# LED_Board.net
KiCad netlist of a schematic drawn in Altium Designer
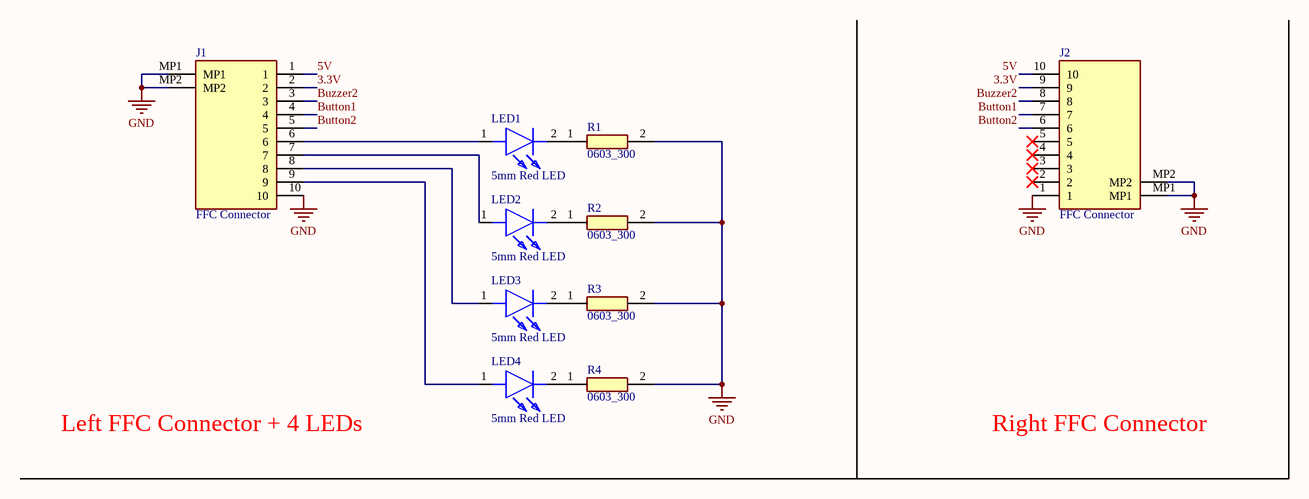
[diagram p0: LED Board.SchDoc]

(export (version "E")
  (design (tool "Eeschema 10.0.6"))
  (components
    (comp (ref "J1")
      (value "FFC Connector")
      (footprint "SamacSys:528921033")
      (description "Connector")
      (fields (field (name "MANUFACTURER_PART_NUMBER") "52892-1033"))
      (libsource (lib "") (part "FFC Connector_1"))
    )
    (comp (ref "J2")
      (value "FFC Connector")
      (footprint "SamacSys:528921033")
      (description "Connector")
      (fields (field (name "MANUFACTURER_PART_NUMBER") "52892-1033"))
      (libsource (lib "LED Board SCH Lib") (part "FFC Connector"))
    )
    (comp (ref "LED1")
      (value "5mm Red LED")
      (footprint "TLHR_6400")
      (description "LED")
      (fields (field (name "MANUFACTURER_PART_NUMBER") "TLHR6400"))
      (libsource (lib "LED Board SCH Lib") (part "TLHR6400"))
    )
    (comp (ref "LED2")
      (value "5mm Red LED")
      (footprint "TLHR_6400")
      (description "LED")
      (fields (field (name "MANUFACTURER_PART_NUMBER") "TLHR6400"))
      (libsource (lib "LED Board SCH Lib") (part "TLHR6400"))
    )
    (comp (ref "LED3")
      (value "5mm Red LED")
      (footprint "TLHR_6400")
      (description "LED")
      (fields (field (name "MANUFACTURER_PART_NUMBER") "TLHR6400"))
      (libsource (lib "LED Board SCH Lib") (part "TLHR6400"))
    )
    (comp (ref "LED4")
      (value "5mm Red LED")
      (footprint "TLHR_6400")
      (description "LED")
      (fields (field (name "MANUFACTURER_PART_NUMBER") "TLHR6400"))
      (libsource (lib "LED Board SCH Lib") (part "TLHR6400"))
    )
    (comp (ref "R1")
      (value "0603_300")
      (footprint "SamacSys:ERA3KV_(0603)")
      (description "Resistor")
      (fields (field (name "MANUFACTURER_PART_NUMBER") "ERA-3KEB2403V"))
      (libsource (lib "LED Board SCH Lib") (part "0603_R"))
    )
    (comp (ref "R2")
      (value "0603_300")
      (footprint "SamacSys:ERA3KV_(0603)")
      (description "Resistor")
      (fields (field (name "MANUFACTURER_PART_NUMBER") "ERA-3KEB2403V"))
      (libsource (lib "LED Board SCH Lib") (part "0603_R"))
    )
    (comp (ref "R3")
      (value "0603_300")
      (footprint "SamacSys:ERA3KV_(0603)")
      (description "Resistor")
      (fields (field (name "MANUFACTURER_PART_NUMBER") "ERA-3KEB2403V"))
      (libsource (lib "LED Board SCH Lib") (part "0603_R"))
    )
    (comp (ref "R4")
      (value "0603_300")
      (footprint "SamacSys:ERA3KV_(0603)")
      (description "Resistor")
      (fields (field (name "MANUFACTURER_PART_NUMBER") "ERA-3KEB2403V"))
      (libsource (lib "LED Board SCH Lib") (part "0603_R"))
    )
  )
  (nets
    (net (code "1") (name "/3.3V") (class "Default")
      (node (ref "J1") (pin "2") (pinfunction "2_2") (pintype "passive"))
      (node (ref "J2") (pin "9") (pinfunction "9_9") (pintype "passive"))
    )
    (net (code "2") (name "/5V") (class "Default")
      (node (ref "J1") (pin "1") (pinfunction "1_1") (pintype "passive"))
      (node (ref "J2") (pin "10") (pinfunction "10_10") (pintype "passive"))
    )
    (net (code "3") (name "/Button1") (class "Default")
      (node (ref "J1") (pin "4") (pinfunction "4_4") (pintype "passive"))
      (node (ref "J2") (pin "7") (pinfunction "7_7") (pintype "passive"))
    )
    (net (code "4") (name "/Button2") (class "Default")
      (node (ref "J1") (pin "5") (pinfunction "5_5") (pintype "passive"))
      (node (ref "J2") (pin "6") (pinfunction "6_6") (pintype "passive"))
    )
    (net (code "5") (name "/Buzzer2") (class "Default")
      (node (ref "J1") (pin "3") (pinfunction "3_3") (pintype "passive"))
      (node (ref "J2") (pin "8") (pinfunction "8_8") (pintype "passive"))
    )
    (net (code "6") (name "GND") (class "Default")
      (node (ref "J1") (pin "10") (pinfunction "10_10") (pintype "passive"))
      (node (ref "J1") (pin "MP1") (pinfunction "MP1_MP1") (pintype "passive"))
      (node (ref "J1") (pin "MP2") (pinfunction "MP2_MP2") (pintype "passive"))
      (node (ref "J2") (pin "1") (pinfunction "1_1") (pintype "passive"))
      (node (ref "J2") (pin "MP1") (pinfunction "MP1_MP1") (pintype "passive"))
      (node (ref "J2") (pin "MP2") (pinfunction "MP2_MP2") (pintype "passive"))
      (node (ref "R1") (pin "2") (pinfunction "2_2") (pintype "passive"))
      (node (ref "R2") (pin "2") (pinfunction "2_2") (pintype "passive"))
      (node (ref "R3") (pin "2") (pinfunction "2_2") (pintype "passive"))
      (node (ref "R4") (pin "2") (pinfunction "2_2") (pintype "passive"))
    )
    (net (code "7") (name "Net-(LED1-A)") (class "Default")
      (node (ref "J1") (pin "6") (pinfunction "6_6") (pintype "passive"))
      (node (ref "LED1") (pin "1") (pinfunction "A_1") (pintype "passive"))
    )
    (net (code "8") (name "Net-(LED1-K)") (class "Default")
      (node (ref "LED1") (pin "2") (pinfunction "K_2") (pintype "passive"))
      (node (ref "R1") (pin "1") (pinfunction "1_1") (pintype "passive"))
    )
    (net (code "9") (name "Net-(LED2-A)") (class "Default")
      (node (ref "J1") (pin "7") (pinfunction "7_7") (pintype "passive"))
      (node (ref "LED2") (pin "1") (pinfunction "A_1") (pintype "passive"))
    )
    (net (code "10") (name "Net-(LED2-K)") (class "Default")
      (node (ref "LED2") (pin "2") (pinfunction "K_2") (pintype "passive"))
      (node (ref "R2") (pin "1") (pinfunction "1_1") (pintype "passive"))
    )
    (net (code "11") (name "Net-(LED3-A)") (class "Default")
      (node (ref "J1") (pin "8") (pinfunction "8_8") (pintype "passive"))
      (node (ref "LED3") (pin "1") (pinfunction "A_1") (pintype "passive"))
    )
    (net (code "12") (name "Net-(LED3-K)") (class "Default")
      (node (ref "LED3") (pin "2") (pinfunction "K_2") (pintype "passive"))
      (node (ref "R3") (pin "1") (pinfunction "1_1") (pintype "passive"))
    )
    (net (code "13") (name "Net-(LED4-A)") (class "Default")
      (node (ref "J1") (pin "9") (pinfunction "9_9") (pintype "passive"))
      (node (ref "LED4") (pin "1") (pinfunction "A_1") (pintype "passive"))
    )
    (net (code "14") (name "Net-(LED4-K)") (class "Default")
      (node (ref "LED4") (pin "2") (pinfunction "K_2") (pintype "passive"))
      (node (ref "R4") (pin "1") (pinfunction "1_1") (pintype "passive"))
    )
    (net (code "15") (name "unconnected-(J2-Pad2)") (class "Default")
      (node (ref "J2") (pin "2") (pinfunction "2_2") (pintype "passive+no_connect"))
    )
    (net (code "16") (name "unconnected-(J2-Pad3)") (class "Default")
      (node (ref "J2") (pin "3") (pinfunction "3_3") (pintype "passive+no_connect"))
    )
    (net (code "17") (name "unconnected-(J2-Pad4)") (class "Default")
      (node (ref "J2") (pin "4") (pinfunction "4_4") (pintype "passive+no_connect"))
    )
    (net (code "18") (name "unconnected-(J2-Pad5)") (class "Default")
      (node (ref "J2") (pin "5") (pinfunction "5_5") (pintype "passive+no_connect"))
    )
  )
)
